# smart_headphones_rev_Nov2016.net
KiCad netlist of a schematic drawn in EAGLE
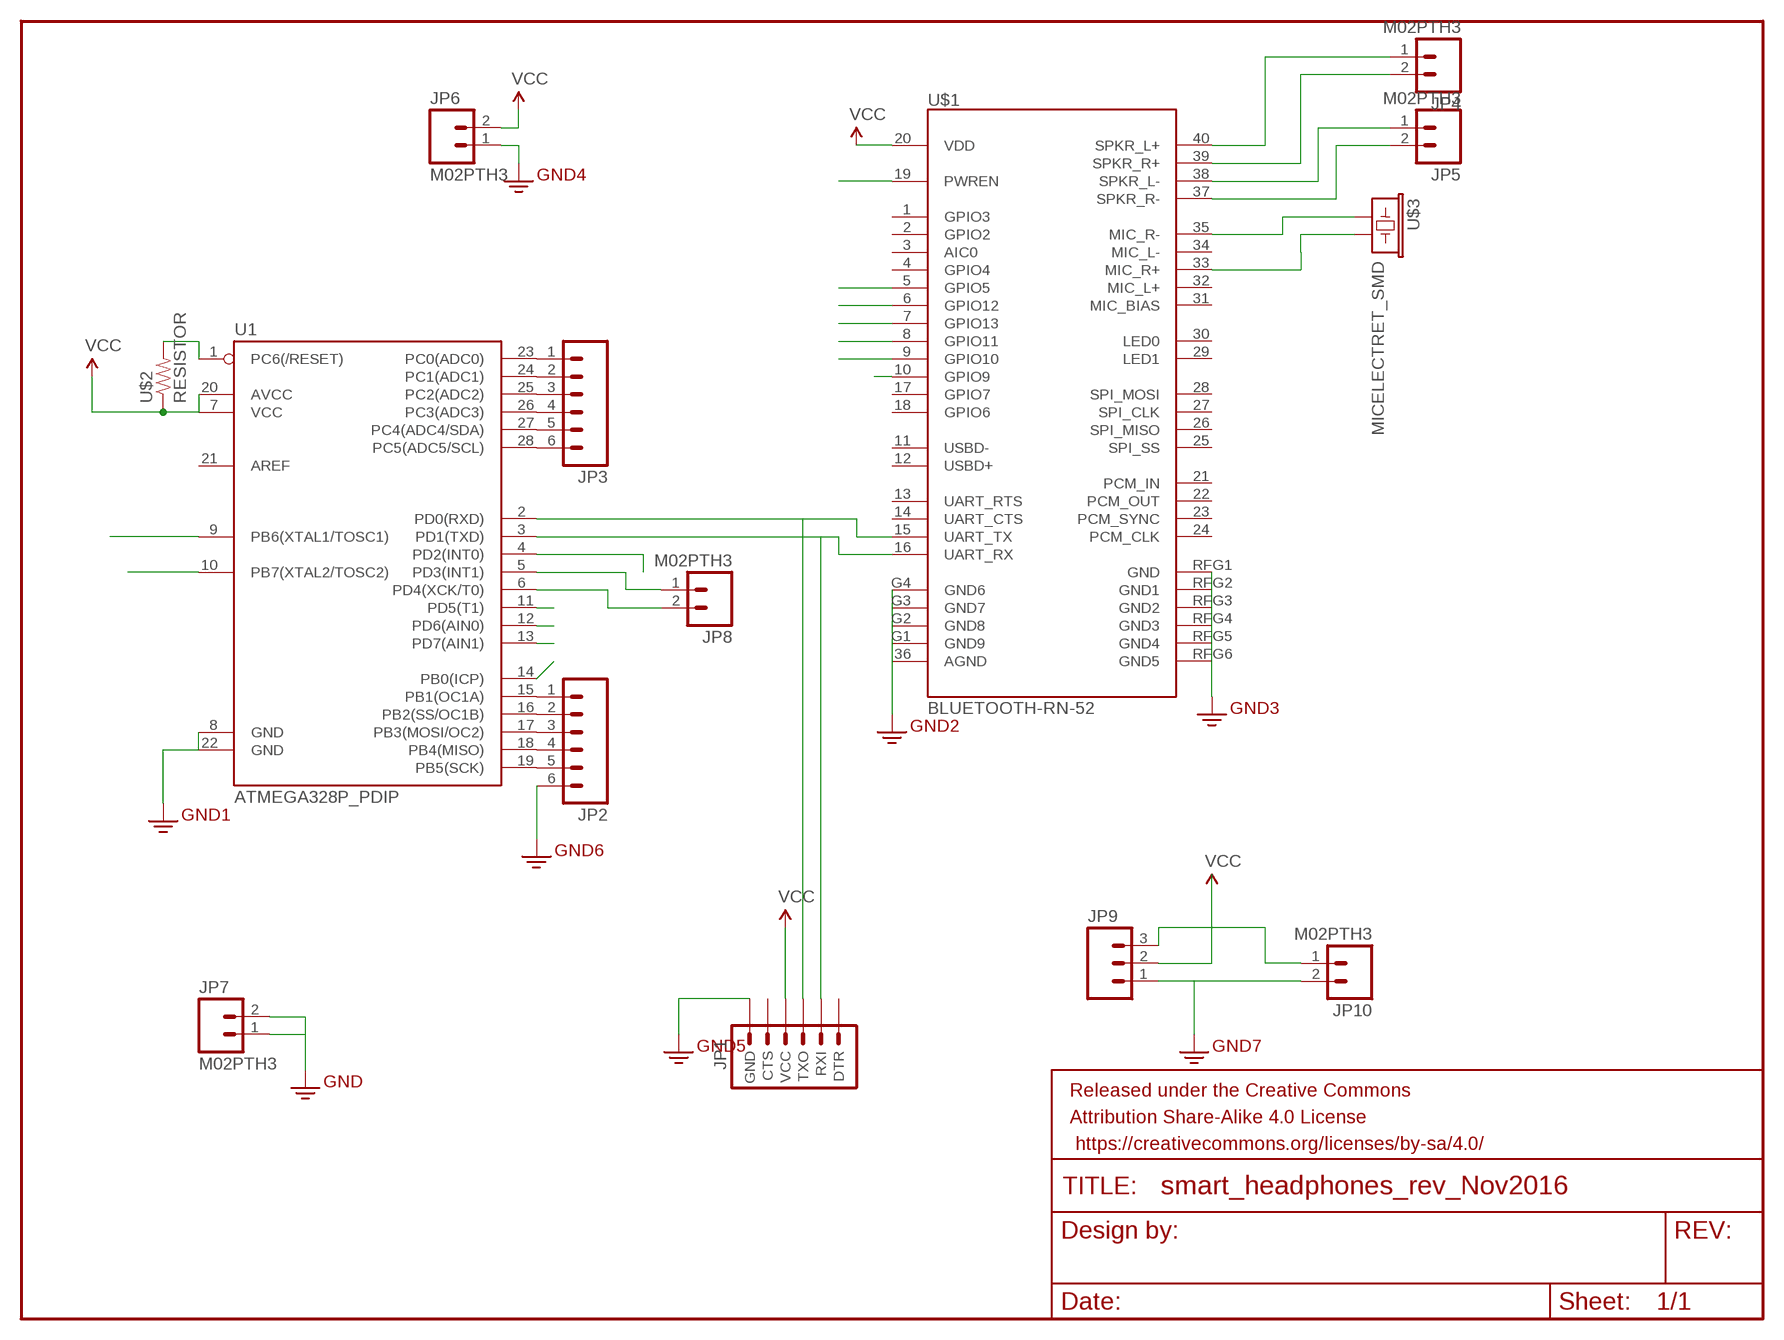
[diagram p0: schematic, sheet 1]

(export (version "E")
  (design (tool "Eeschema 10.0.6"))
  (components
    (comp (ref "JP1")
      (value "FTDI_SERIAL_PROGRAMMER_PORTLONGPADS")
      (footprint "eagle-import:1X06_LONGPADS")
      (libsource (lib "eagle-import") (part "FTDI_SERIAL_PROGRAMMER_PORTLONGPADS"))
    )
    (comp (ref "JP2")
      (value "M06LONGPADS")
      (footprint "eagle-import:1X06_LONGPADS")
      (libsource (lib "eagle-import") (part "M06LONGPADS"))
    )
    (comp (ref "JP3")
      (value "M06LONGPADS")
      (footprint "eagle-import:1X06_LONGPADS")
      (libsource (lib "eagle-import") (part "M06LONGPADS"))
    )
    (comp (ref "JP4")
      (value "M02PTH3")
      (footprint "eagle-import:1X02_LONGPADS")
      (libsource (lib "eagle-import") (part "M02PTH3"))
    )
    (comp (ref "JP5")
      (value "M02PTH3")
      (footprint "eagle-import:1X02_LONGPADS")
      (libsource (lib "eagle-import") (part "M02PTH3"))
    )
    (comp (ref "JP6")
      (value "M02PTH3")
      (footprint "eagle-import:1X02_LONGPADS")
      (libsource (lib "eagle-import") (part "M02PTH3"))
    )
    (comp (ref "JP7")
      (value "M02PTH3")
      (footprint "eagle-import:1X02_LONGPADS")
      (libsource (lib "eagle-import") (part "M02PTH3"))
    )
    (comp (ref "JP8")
      (value "M02PTH3")
      (footprint "eagle-import:1X02_LONGPADS")
      (libsource (lib "eagle-import") (part "M02PTH3"))
    )
    (comp (ref "JP9")
      (value "M03LONGPADS")
      (footprint "eagle-import:1X03_LONGPADS")
      (libsource (lib "eagle-import") (part "M03LONGPADS"))
    )
    (comp (ref "JP10")
      (value "M02PTH3")
      (footprint "eagle-import:1X02_LONGPADS")
      (libsource (lib "eagle-import") (part "M02PTH3"))
    )
    (comp (ref "U$1")
      (value "BLUETOOTH-RN-52")
      (footprint "eagle-import:RN-52")
      (libsource (lib "eagle-import") (part "BLUETOOTH-RN-52"))
    )
    (comp (ref "U$2")
      (value "RESISTOR")
      (footprint "eagle-import:0805")
      (libsource (lib "eagle-import") (part "RESISTOR"))
    )
    (comp (ref "U$3")
      (value "MICELECTRET_SMD")
      (footprint "eagle-import:MIC_ELECTRET_SMD")
      (libsource (lib "eagle-import") (part "MICELECTRET_SMD"))
    )
    (comp (ref "U1")
      (value "ATMEGA328P_PDIP")
      (footprint "eagle-import:DIP28")
      (libsource (lib "eagle-import") (part "ATMEGA328P_PDIP"))
    )
  )
  (nets
    (net (code "1") (name "/PB0") (class "Default")
      (node (ref "U$1") (pin "5") (pinfunction "GPIO5_5") (pintype "bidirectional"))
      (node (ref "U1") (pin "14") (pinfunction "PB0(ICP)_14") (pintype "bidirectional"))
    )
    (net (code "2") (name "/PB6") (class "Default")
      (node (ref "U$1") (pin "10") (pinfunction "GPIO9_10") (pintype "bidirectional"))
      (node (ref "U1") (pin "9") (pinfunction "PB6(XTAL1/TOSC1)_9") (pintype "bidirectional"))
    )
    (net (code "3") (name "/PB7") (class "Default")
      (node (ref "U$1") (pin "9") (pinfunction "GPIO10_9") (pintype "bidirectional"))
      (node (ref "U1") (pin "10") (pinfunction "PB7(XTAL2/TOSC2)_10") (pintype "bidirectional"))
    )
    (net (code "4") (name "/PD5") (class "Default")
      (node (ref "U$1") (pin "8") (pinfunction "GPIO11_8") (pintype "bidirectional"))
      (node (ref "U1") (pin "11") (pinfunction "PD5(T1)_11") (pintype "bidirectional"))
    )
    (net (code "5") (name "/PD6") (class "Default")
      (node (ref "U$1") (pin "7") (pinfunction "GPIO13_7") (pintype "bidirectional"))
      (node (ref "U1") (pin "12") (pinfunction "PD6(AIN0)_12") (pintype "bidirectional"))
    )
    (net (code "6") (name "/PD7") (class "Default")
      (node (ref "U$1") (pin "6") (pinfunction "GPIO12_6") (pintype "bidirectional"))
      (node (ref "U1") (pin "13") (pinfunction "PD7(AIN1)_13") (pintype "bidirectional"))
    )
    (net (code "7") (name "/PWREN") (class "Default")
      (node (ref "U$1") (pin "19") (pinfunction "PWREN_19") (pintype "bidirectional"))
      (node (ref "U1") (pin "4") (pinfunction "PD2(INT0)_4") (pintype "bidirectional"))
    )
    (net (code "8") (name "GND") (class "Default")
      (node (ref "JP1") (pin "6") (pinfunction "GND_6") (pintype "passive"))
      (node (ref "JP10") (pin "2") (pinfunction "2_2") (pintype "passive"))
      (node (ref "JP2") (pin "6") (pinfunction "6_6") (pintype "passive"))
      (node (ref "JP6") (pin "1") (pinfunction "1_1") (pintype "passive"))
      (node (ref "JP7") (pin "1") (pinfunction "1_1") (pintype "passive"))
      (node (ref "JP7") (pin "2") (pinfunction "2_2") (pintype "passive"))
      (node (ref "JP9") (pin "1") (pinfunction "1_1") (pintype "passive"))
      (node (ref "U$1") (pin "36") (pinfunction "AGND_36") (pintype "bidirectional"))
      (node (ref "U$1") (pin "G1") (pinfunction "GND9_G1") (pintype "bidirectional"))
      (node (ref "U$1") (pin "G2") (pinfunction "GND8_G2") (pintype "bidirectional"))
      (node (ref "U$1") (pin "G3") (pinfunction "GND7_G3") (pintype "bidirectional"))
      (node (ref "U$1") (pin "G4") (pinfunction "GND6_G4") (pintype "bidirectional"))
      (node (ref "U$1") (pin "RFG1") (pinfunction "GND_RFG1") (pintype "bidirectional"))
      (node (ref "U$1") (pin "RFG2") (pinfunction "GND1_RFG2") (pintype "bidirectional"))
      (node (ref "U$1") (pin "RFG3") (pinfunction "GND2_RFG3") (pintype "bidirectional"))
      (node (ref "U$1") (pin "RFG4") (pinfunction "GND3_RFG4") (pintype "bidirectional"))
      (node (ref "U$1") (pin "RFG5") (pinfunction "GND4_RFG5") (pintype "bidirectional"))
      (node (ref "U$1") (pin "RFG6") (pinfunction "GND5_RFG6") (pintype "bidirectional"))
      (node (ref "U1") (pin "22") (pinfunction "GND_22") (pintype "bidirectional"))
      (node (ref "U1") (pin "8") (pinfunction "GND_8") (pintype "bidirectional"))
    )
    (net (code "9") (name "Net-(JP1-RXI)") (class "Default")
      (node (ref "JP1") (pin "2") (pinfunction "RXI_2") (pintype "passive"))
      (node (ref "U$1") (pin "16") (pinfunction "UART_RX_16") (pintype "bidirectional"))
      (node (ref "U1") (pin "3") (pinfunction "PD1(TXD)_3") (pintype "bidirectional"))
    )
    (net (code "10") (name "Net-(JP1-TXO)") (class "Default")
      (node (ref "JP1") (pin "3") (pinfunction "TXO_3") (pintype "passive"))
      (node (ref "U$1") (pin "15") (pinfunction "UART_TX_15") (pintype "bidirectional"))
      (node (ref "U1") (pin "2") (pinfunction "PD0(RXD)_2") (pintype "bidirectional"))
    )
    (net (code "11") (name "Net-(JP10-Pad1)") (class "Default")
      (node (ref "JP10") (pin "1") (pinfunction "1_1") (pintype "passive"))
      (node (ref "JP9") (pin "3") (pinfunction "3_3") (pintype "passive"))
    )
    (net (code "12") (name "Net-(U$1-MIC_R+)") (class "Default")
      (node (ref "U$1") (pin "33") (pinfunction "MIC_R+_33") (pintype "bidirectional"))
      (node (ref "U$3") (pin "2") (pinfunction "2_2") (pintype "passive"))
    )
    (net (code "13") (name "Net-(U$1-MIC_R-)") (class "Default")
      (node (ref "U$1") (pin "35") (pinfunction "MIC_R-_35") (pintype "bidirectional"))
      (node (ref "U$3") (pin "1") (pinfunction "1_1") (pintype "passive"))
    )
    (net (code "14") (name "Net-(U$1-SPKR_L+)") (class "Default")
      (node (ref "JP4") (pin "1") (pinfunction "1_1") (pintype "passive"))
      (node (ref "U$1") (pin "40") (pinfunction "SPKR_L+_40") (pintype "bidirectional"))
    )
    (net (code "15") (name "Net-(U$1-SPKR_L-)") (class "Default")
      (node (ref "JP5") (pin "1") (pinfunction "1_1") (pintype "passive"))
      (node (ref "U$1") (pin "38") (pinfunction "SPKR_L-_38") (pintype "bidirectional"))
    )
    (net (code "16") (name "Net-(U$1-SPKR_R+)") (class "Default")
      (node (ref "JP4") (pin "2") (pinfunction "2_2") (pintype "passive"))
      (node (ref "U$1") (pin "39") (pinfunction "SPKR_R+_39") (pintype "bidirectional"))
    )
    (net (code "17") (name "Net-(U$1-SPKR_R-)") (class "Default")
      (node (ref "JP5") (pin "2") (pinfunction "2_2") (pintype "passive"))
      (node (ref "U$1") (pin "37") (pinfunction "SPKR_R-_37") (pintype "bidirectional"))
    )
    (net (code "18") (name "Net-(U1-PB1(OC1A))") (class "Default")
      (node (ref "JP2") (pin "1") (pinfunction "1_1") (pintype "passive"))
      (node (ref "U1") (pin "15") (pinfunction "PB1(OC1A)_15") (pintype "bidirectional"))
    )
    (net (code "19") (name "Net-(U1-PB2(SS{slash}OC1B))") (class "Default")
      (node (ref "JP2") (pin "2") (pinfunction "2_2") (pintype "passive"))
      (node (ref "U1") (pin "16") (pinfunction "PB2(SS/OC1B)_16") (pintype "bidirectional"))
    )
    (net (code "20") (name "Net-(U1-PB3(MOSI{slash}OC2))") (class "Default")
      (node (ref "JP2") (pin "3") (pinfunction "3_3") (pintype "passive"))
      (node (ref "U1") (pin "17") (pinfunction "PB3(MOSI/OC2)_17") (pintype "bidirectional"))
    )
    (net (code "21") (name "Net-(U1-PB4(MISO))") (class "Default")
      (node (ref "JP2") (pin "4") (pinfunction "4_4") (pintype "passive"))
      (node (ref "U1") (pin "18") (pinfunction "PB4(MISO)_18") (pintype "bidirectional"))
    )
    (net (code "22") (name "Net-(U1-PB5(SCK))") (class "Default")
      (node (ref "JP2") (pin "5") (pinfunction "5_5") (pintype "passive"))
      (node (ref "U1") (pin "19") (pinfunction "PB5(SCK)_19") (pintype "bidirectional"))
    )
    (net (code "23") (name "Net-(U1-PC0(ADC0))") (class "Default")
      (node (ref "JP3") (pin "1") (pinfunction "1_1") (pintype "passive"))
      (node (ref "U1") (pin "23") (pinfunction "PC0(ADC0)_23") (pintype "bidirectional"))
    )
    (net (code "24") (name "Net-(U1-PC1(ADC1))") (class "Default")
      (node (ref "JP3") (pin "2") (pinfunction "2_2") (pintype "passive"))
      (node (ref "U1") (pin "24") (pinfunction "PC1(ADC1)_24") (pintype "bidirectional"))
    )
    (net (code "25") (name "Net-(U1-PC2(ADC2))") (class "Default")
      (node (ref "JP3") (pin "3") (pinfunction "3_3") (pintype "passive"))
      (node (ref "U1") (pin "25") (pinfunction "PC2(ADC2)_25") (pintype "bidirectional"))
    )
    (net (code "26") (name "Net-(U1-PC3(ADC3))") (class "Default")
      (node (ref "JP3") (pin "4") (pinfunction "4_4") (pintype "passive"))
      (node (ref "U1") (pin "26") (pinfunction "PC3(ADC3)_26") (pintype "bidirectional"))
    )
    (net (code "27") (name "Net-(U1-PC4(ADC4{slash}SDA))") (class "Default")
      (node (ref "JP3") (pin "5") (pinfunction "5_5") (pintype "passive"))
      (node (ref "U1") (pin "27") (pinfunction "PC4(ADC4/SDA)_27") (pintype "bidirectional"))
    )
    (net (code "28") (name "Net-(U1-PC5(ADC5{slash}SCL))") (class "Default")
      (node (ref "JP3") (pin "6") (pinfunction "6_6") (pintype "passive"))
      (node (ref "U1") (pin "28") (pinfunction "PC5(ADC5/SCL)_28") (pintype "bidirectional"))
    )
    (net (code "29") (name "Net-(U1-PC6({slash}RESET))") (class "Default")
      (node (ref "U$2") (pin "2") (pinfunction "2_2") (pintype "passive"))
      (node (ref "U1") (pin "1") (pinfunction "PC6(/RESET)_1") (pintype "bidirectional"))
    )
    (net (code "30") (name "Net-(U1-PD3(INT1))") (class "Default")
      (node (ref "JP8") (pin "1") (pinfunction "1_1") (pintype "passive"))
      (node (ref "U1") (pin "5") (pinfunction "PD3(INT1)_5") (pintype "bidirectional"))
    )
    (net (code "31") (name "Net-(U1-PD4(XCK{slash}T0))") (class "Default")
      (node (ref "JP8") (pin "2") (pinfunction "2_2") (pintype "passive"))
      (node (ref "U1") (pin "6") (pinfunction "PD4(XCK/T0)_6") (pintype "bidirectional"))
    )
    (net (code "32") (name "VCC") (class "Default")
      (node (ref "JP1") (pin "4") (pinfunction "VCC_4") (pintype "passive"))
      (node (ref "JP6") (pin "2") (pinfunction "2_2") (pintype "passive"))
      (node (ref "JP9") (pin "2") (pinfunction "2_2") (pintype "passive"))
      (node (ref "U$1") (pin "20") (pinfunction "VDD_20") (pintype "bidirectional"))
      (node (ref "U$2") (pin "1") (pinfunction "1_1") (pintype "passive"))
      (node (ref "U1") (pin "20") (pinfunction "AVCC_20") (pintype "bidirectional"))
      (node (ref "U1") (pin "7") (pinfunction "VCC_7") (pintype "bidirectional"))
    )
    (net (code "33") (name "unconnected-(JP1-CTS-Pad5)") (class "Default")
      (node (ref "JP1") (pin "5") (pinfunction "CTS_5") (pintype "passive"))
    )
    (net (code "34") (name "unconnected-(JP1-DTR-Pad1)") (class "Default")
      (node (ref "JP1") (pin "1") (pinfunction "DTR_1") (pintype "passive"))
    )
    (net (code "35") (name "unconnected-(U$1-AIC0-Pad3)") (class "Default")
      (node (ref "U$1") (pin "3") (pinfunction "AIC0_3") (pintype "bidirectional"))
    )
    (net (code "36") (name "unconnected-(U$1-GPIO2-Pad2)") (class "Default")
      (node (ref "U$1") (pin "2") (pinfunction "GPIO2_2") (pintype "bidirectional"))
    )
    (net (code "37") (name "unconnected-(U$1-GPIO3-Pad1)") (class "Default")
      (node (ref "U$1") (pin "1") (pinfunction "GPIO3_1") (pintype "bidirectional"))
    )
    (net (code "38") (name "unconnected-(U$1-GPIO4-Pad4)") (class "Default")
      (node (ref "U$1") (pin "4") (pinfunction "GPIO4_4") (pintype "bidirectional"))
    )
    (net (code "39") (name "unconnected-(U$1-GPIO6-Pad18)") (class "Default")
      (node (ref "U$1") (pin "18") (pinfunction "GPIO6_18") (pintype "bidirectional"))
    )
    (net (code "40") (name "unconnected-(U$1-GPIO7-Pad17)") (class "Default")
      (node (ref "U$1") (pin "17") (pinfunction "GPIO7_17") (pintype "bidirectional"))
    )
    (net (code "41") (name "unconnected-(U$1-LED0-Pad30)") (class "Default")
      (node (ref "U$1") (pin "30") (pinfunction "LED0_30") (pintype "bidirectional"))
    )
    (net (code "42") (name "unconnected-(U$1-LED1-Pad29)") (class "Default")
      (node (ref "U$1") (pin "29") (pinfunction "LED1_29") (pintype "bidirectional"))
    )
    (net (code "43") (name "unconnected-(U$1-MIC_BIAS-Pad31)") (class "Default")
      (node (ref "U$1") (pin "31") (pinfunction "MIC_BIAS_31") (pintype "bidirectional"))
    )
    (net (code "44") (name "unconnected-(U$1-MIC_L+-Pad32)") (class "Default")
      (node (ref "U$1") (pin "32") (pinfunction "MIC_L+_32") (pintype "bidirectional"))
    )
    (net (code "45") (name "unconnected-(U$1-MIC_L--Pad34)") (class "Default")
      (node (ref "U$1") (pin "34") (pinfunction "MIC_L-_34") (pintype "bidirectional"))
    )
    (net (code "46") (name "unconnected-(U$1-PCM_CLK-Pad24)") (class "Default")
      (node (ref "U$1") (pin "24") (pinfunction "PCM_CLK_24") (pintype "bidirectional"))
    )
    (net (code "47") (name "unconnected-(U$1-PCM_IN-Pad21)") (class "Default")
      (node (ref "U$1") (pin "21") (pinfunction "PCM_IN_21") (pintype "bidirectional"))
    )
    (net (code "48") (name "unconnected-(U$1-PCM_OUT-Pad22)") (class "Default")
      (node (ref "U$1") (pin "22") (pinfunction "PCM_OUT_22") (pintype "bidirectional"))
    )
    (net (code "49") (name "unconnected-(U$1-PCM_SYNC-Pad23)") (class "Default")
      (node (ref "U$1") (pin "23") (pinfunction "PCM_SYNC_23") (pintype "bidirectional"))
    )
    (net (code "50") (name "unconnected-(U$1-SPI_CLK-Pad27)") (class "Default")
      (node (ref "U$1") (pin "27") (pinfunction "SPI_CLK_27") (pintype "bidirectional"))
    )
    (net (code "51") (name "unconnected-(U$1-SPI_MISO-Pad26)") (class "Default")
      (node (ref "U$1") (pin "26") (pinfunction "SPI_MISO_26") (pintype "bidirectional"))
    )
    (net (code "52") (name "unconnected-(U$1-SPI_MOSI-Pad28)") (class "Default")
      (node (ref "U$1") (pin "28") (pinfunction "SPI_MOSI_28") (pintype "bidirectional"))
    )
    (net (code "53") (name "unconnected-(U$1-SPI_SS-Pad25)") (class "Default")
      (node (ref "U$1") (pin "25") (pinfunction "SPI_SS_25") (pintype "bidirectional"))
    )
    (net (code "54") (name "unconnected-(U$1-UART_CTS-Pad14)") (class "Default")
      (node (ref "U$1") (pin "14") (pinfunction "UART_CTS_14") (pintype "bidirectional"))
    )
    (net (code "55") (name "unconnected-(U$1-UART_RTS-Pad13)") (class "Default")
      (node (ref "U$1") (pin "13") (pinfunction "UART_RTS_13") (pintype "bidirectional"))
    )
    (net (code "56") (name "unconnected-(U$1-USBD+-Pad12)") (class "Default")
      (node (ref "U$1") (pin "12") (pinfunction "USBD+_12") (pintype "bidirectional"))
    )
    (net (code "57") (name "unconnected-(U$1-USBD--Pad11)") (class "Default")
      (node (ref "U$1") (pin "11") (pinfunction "USBD-_11") (pintype "bidirectional"))
    )
    (net (code "58") (name "unconnected-(U1-AREF-Pad21)") (class "Default")
      (node (ref "U1") (pin "21") (pinfunction "AREF_21") (pintype "bidirectional"))
    )
  )
)
